# univ_3-7-0-x-rev4.net
KiCad netlist of a schematic drawn in EAGLE
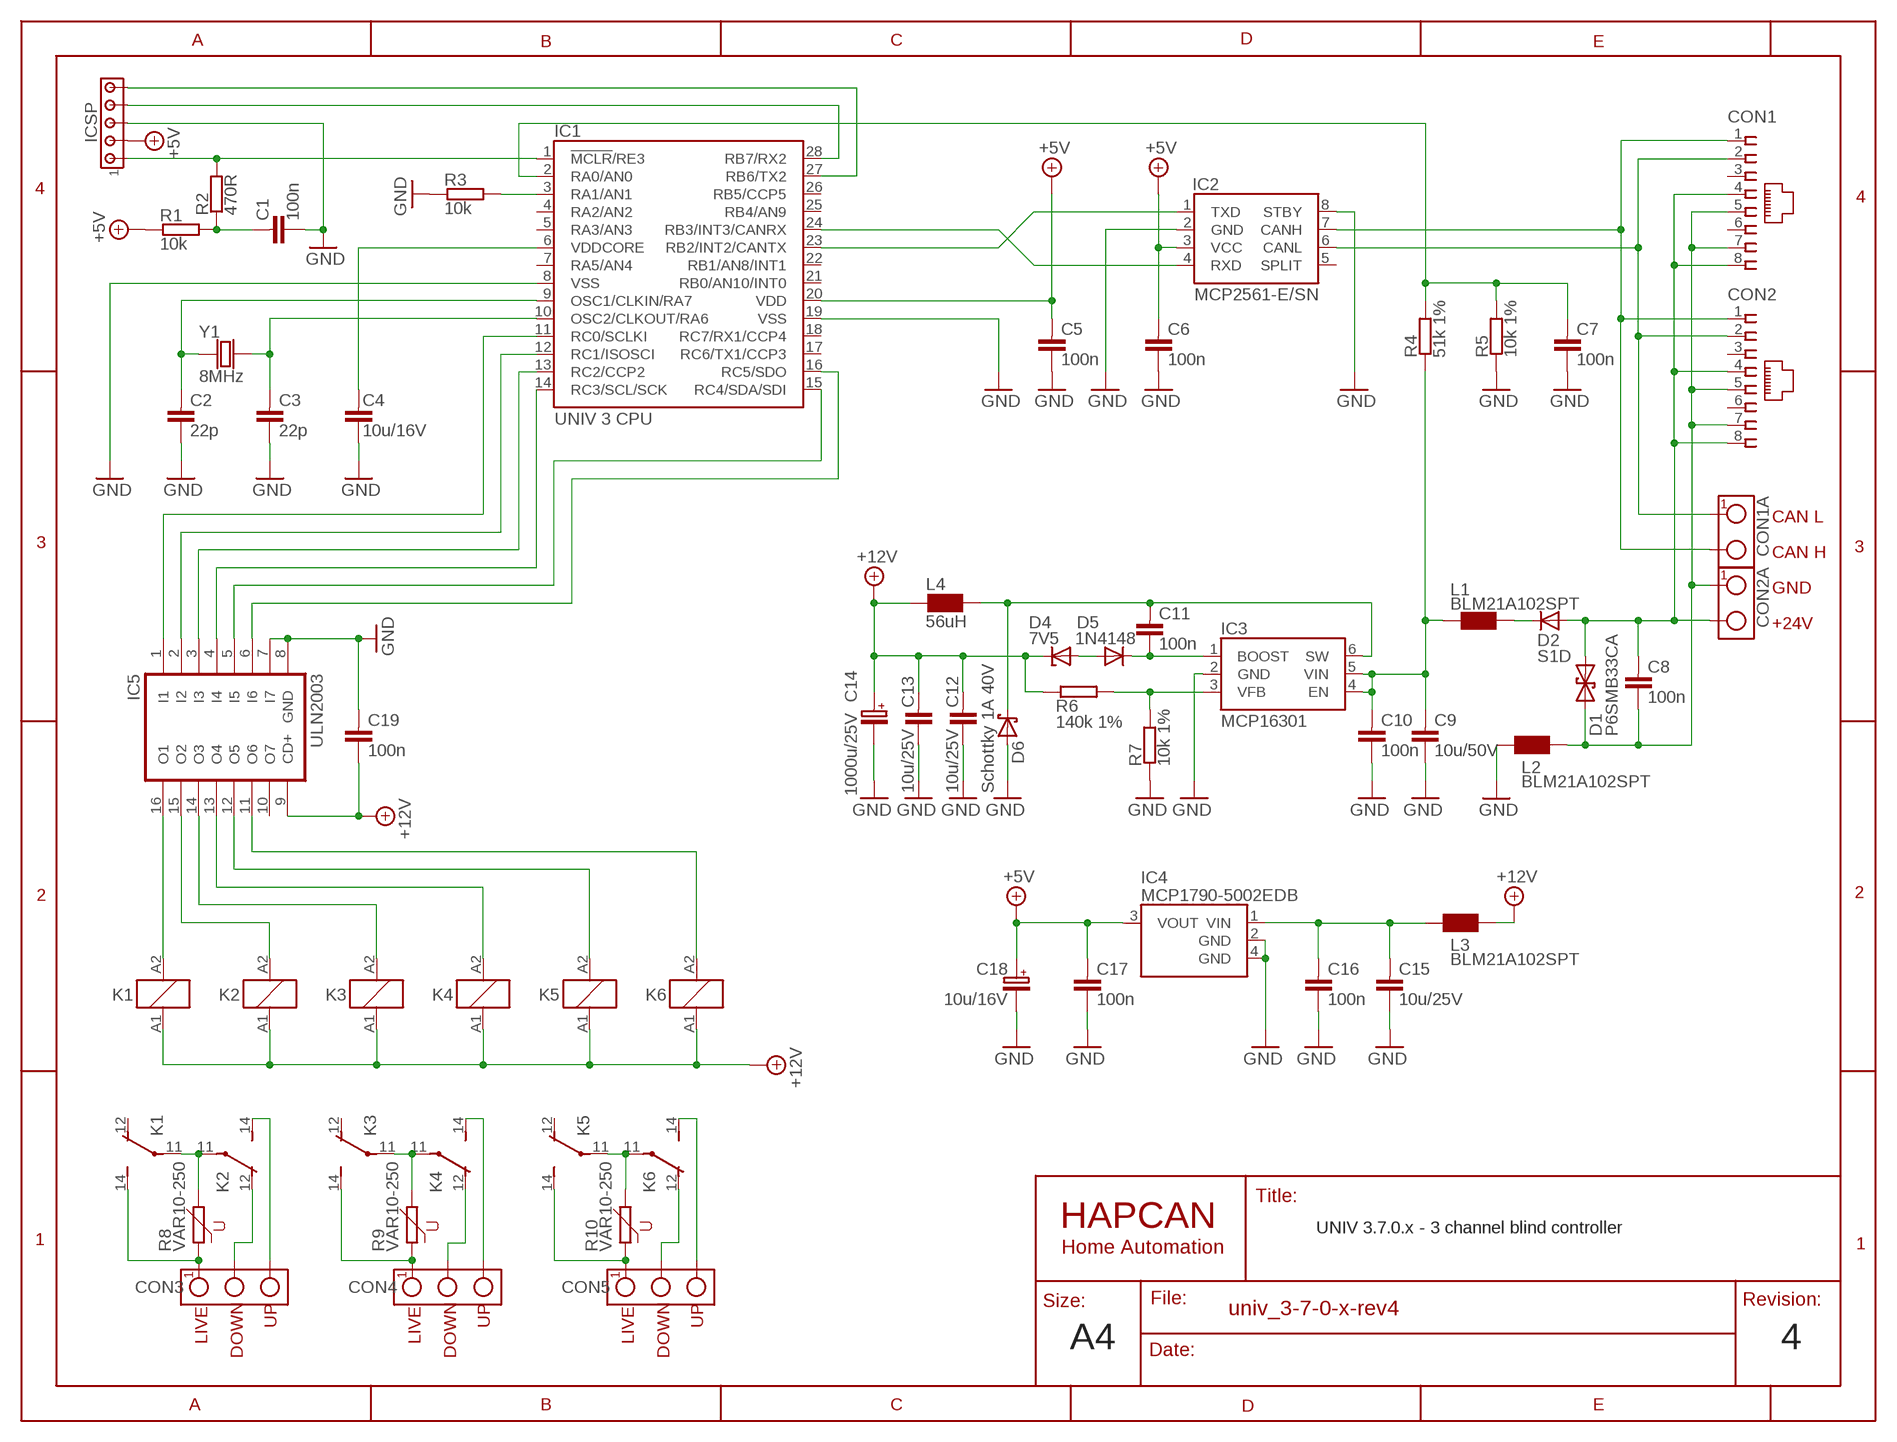
[diagram p0: schematic, sheet 1]

(export (version "E")
  (design (tool "Eeschema 10.0.6"))
  (components
    (comp (ref "C1")
      (value "100n")
      (footprint "eagle-import:0805")
      (libsource (lib "eagle-import") (part "CAPACITOR0805"))
    )
    (comp (ref "C2")
      (value "22p")
      (footprint "eagle-import:0805")
      (libsource (lib "eagle-import") (part "CAPACITOR0805"))
    )
    (comp (ref "C3")
      (value "22p")
      (footprint "eagle-import:0805")
      (libsource (lib "eagle-import") (part "CAPACITOR0805"))
    )
    (comp (ref "C4")
      (value "10u/16V")
      (footprint "eagle-import:0805")
      (libsource (lib "eagle-import") (part "CAPACITOR0805"))
    )
    (comp (ref "C5")
      (value "100n")
      (footprint "eagle-import:0805")
      (libsource (lib "eagle-import") (part "CAPACITOR0805"))
    )
    (comp (ref "C6")
      (value "100n")
      (footprint "eagle-import:0805")
      (libsource (lib "eagle-import") (part "CAPACITOR0805"))
    )
    (comp (ref "C7")
      (value "100n")
      (footprint "eagle-import:0805")
      (libsource (lib "eagle-import") (part "CAPACITOR0805"))
    )
    (comp (ref "C8")
      (value "100n")
      (footprint "eagle-import:0805")
      (libsource (lib "eagle-import") (part "CAPACITOR0805"))
    )
    (comp (ref "C9")
      (value "10u/50V")
      (footprint "eagle-import:1210")
      (libsource (lib "eagle-import") (part "CAPACITOR1210"))
    )
    (comp (ref "C10")
      (value "100n")
      (footprint "eagle-import:0805")
      (libsource (lib "eagle-import") (part "CAPACITOR0805"))
    )
    (comp (ref "C11")
      (value "100n")
      (footprint "eagle-import:0805")
      (libsource (lib "eagle-import") (part "CAPACITOR0805"))
    )
    (comp (ref "C12")
      (value "10u/25V")
      (footprint "eagle-import:1206")
      (libsource (lib "eagle-import") (part "CAPACITOR1206"))
    )
    (comp (ref "C13")
      (value "10u/25V")
      (footprint "eagle-import:1206")
      (libsource (lib "eagle-import") (part "CAPACITOR1206"))
    )
    (comp (ref "C14")
      (value "1000u/25V")
      (footprint "eagle-import:CAP-5X10.5")
      (libsource (lib "eagle-import") (part "CAPACITOR-POLARIZED-5X10.5"))
    )
    (comp (ref "C15")
      (value "10u/25V")
      (footprint "eagle-import:1206")
      (libsource (lib "eagle-import") (part "CAPACITOR1206"))
    )
    (comp (ref "C16")
      (value "100n")
      (footprint "eagle-import:0805")
      (libsource (lib "eagle-import") (part "CAPACITOR0805"))
    )
    (comp (ref "C17")
      (value "100n")
      (footprint "eagle-import:0805")
      (libsource (lib "eagle-import") (part "CAPACITOR0805"))
    )
    (comp (ref "C18")
      (value "10u/16V")
      (footprint "eagle-import:SMC_B")
      (libsource (lib "eagle-import") (part "CAPACITOR-POLARIZED-SMC_B"))
    )
    (comp (ref "C19")
      (value "100n")
      (footprint "eagle-import:0805")
      (libsource (lib "eagle-import") (part "CAPACITOR0805"))
    )
    (comp (ref "CON1")
      (value "RJ45-SOCKET")
      (footprint "eagle-import:RJ45-PCB-SOCKET")
      (libsource (lib "eagle-import") (part "RJ45-SOCKET"))
    )
    (comp (ref "CON1A")
      (value "TERMINAL-2")
      (footprint "eagle-import:ARK2-5X10,5MM")
      (libsource (lib "eagle-import") (part "TERMINAL-2-5X10,5MM"))
    )
    (comp (ref "CON2")
      (value "RJ45-SOCKET")
      (footprint "eagle-import:RJ45-PCB-SOCKET")
      (libsource (lib "eagle-import") (part "RJ45-SOCKET"))
    )
    (comp (ref "CON2A")
      (value "TERMINAL-2")
      (footprint "eagle-import:ARK2-5X10,5MM")
      (libsource (lib "eagle-import") (part "TERMINAL-2-5X10,5MM"))
    )
    (comp (ref "CON3")
      (value "TERMINAL-3-5X10.5MM")
      (footprint "eagle-import:ARK3-5X10.5MM")
      (libsource (lib "eagle-import") (part "TERMINAL-3-5X10.5MM"))
    )
    (comp (ref "CON4")
      (value "TERMINAL-3-5X10.5MM")
      (footprint "eagle-import:ARK3-5X10.5MM")
      (libsource (lib "eagle-import") (part "TERMINAL-3-5X10.5MM"))
    )
    (comp (ref "CON5")
      (value "TERMINAL-3-5X10.5MM")
      (footprint "eagle-import:ARK3-5X10.5MM")
      (libsource (lib "eagle-import") (part "TERMINAL-3-5X10.5MM"))
    )
    (comp (ref "D1")
      (value "P6SMB33CA")
      (footprint "eagle-import:DO-214_TRANSIL2")
      (libsource (lib "eagle-import") (part "DIODE_TRANSIL2"))
    )
    (comp (ref "D2")
      (value "S1D")
      (footprint "eagle-import:DO-214")
      (libsource (lib "eagle-import") (part "DIODE_DO-214"))
    )
    (comp (ref "D4")
      (value "7V5")
      (footprint "eagle-import:SOD-80")
      (libsource (lib "eagle-import") (part "DIODE_ZENER_SOD-80"))
    )
    (comp (ref "D5")
      (value "1N4148")
      (footprint "eagle-import:0805")
      (libsource (lib "eagle-import") (part "DIODE_0805"))
    )
    (comp (ref "D6")
      (value "Schottky 1A 40V")
      (footprint "eagle-import:DO-214")
      (libsource (lib "eagle-import") (part "DIODE_TRANSIL1_DO214"))
    )
    (comp (ref "IC1")
      (value "UNIV 3 CPU")
      (footprint "eagle-import:UNIV3CPU")
      (libsource (lib "eagle-import") (part "UNIV3CPU-I/SO"))
    )
    (comp (ref "IC2")
      (value "MCP2561-E/SN")
      (footprint "eagle-import:SO-08")
      (libsource (lib "eagle-import") (part "MCP2561-E/SN"))
    )
    (comp (ref "IC3")
      (value "MCP16301")
      (footprint "eagle-import:SOT-23-6")
      (libsource (lib "eagle-import") (part "MCP16301SOT23-6"))
    )
    (comp (ref "IC4")
      (value "MCP1790-5002EDB")
      (footprint "eagle-import:SOT-223")
      (libsource (lib "eagle-import") (part "MCP1826SOT223-3"))
    )
    (comp (ref "IC5")
      (value "ULN2003")
      (footprint "eagle-import:SO-16")
      (libsource (lib "eagle-import") (part "ULN2003"))
    )
    (comp (ref "ICSP")
      (value "HEADER5")
      (footprint "eagle-import:SIP-5")
      (libsource (lib "eagle-import") (part "HEADER5"))
    )
    (comp (ref "K1")
      (value "RELAY_SNR_SPDTV")
      (footprint "eagle-import:RELAY_SNR_SPDT_V")
      (libsource (lib "eagle-import") (part "RELAY_SNR_SPDTV"))
    )
    (comp (ref "K2")
      (value "RELAY_SNR_SPDTV")
      (footprint "eagle-import:RELAY_SNR_SPDT_V")
      (libsource (lib "eagle-import") (part "RELAY_SNR_SPDTV"))
    )
    (comp (ref "K3")
      (value "RELAY_SNR_SPDTV")
      (footprint "eagle-import:RELAY_SNR_SPDT_V")
      (libsource (lib "eagle-import") (part "RELAY_SNR_SPDTV"))
    )
    (comp (ref "K4")
      (value "RELAY_SNR_SPDTV")
      (footprint "eagle-import:RELAY_SNR_SPDT_V")
      (libsource (lib "eagle-import") (part "RELAY_SNR_SPDTV"))
    )
    (comp (ref "K5")
      (value "RELAY_SNR_SPDTV")
      (footprint "eagle-import:RELAY_SNR_SPDT_V")
      (libsource (lib "eagle-import") (part "RELAY_SNR_SPDTV"))
    )
    (comp (ref "K6")
      (value "RELAY_SNR_SPDTV")
      (footprint "eagle-import:RELAY_SNR_SPDT_V")
      (libsource (lib "eagle-import") (part "RELAY_SNR_SPDTV"))
    )
    (comp (ref "L1")
      (value "BLM21A102SPT")
      (footprint "eagle-import:0805")
      (libsource (lib "eagle-import") (part "CHOKE0805"))
    )
    (comp (ref "L2")
      (value "BLM21A102SPT")
      (footprint "eagle-import:0805")
      (libsource (lib "eagle-import") (part "CHOKE0805"))
    )
    (comp (ref "L3")
      (value "BLM21A102SPT")
      (footprint "eagle-import:0805")
      (libsource (lib "eagle-import") (part "CHOKE0805"))
    )
    (comp (ref "L4")
      (value "56uH")
      (footprint "eagle-import:CHOKE-DER0705")
      (libsource (lib "eagle-import") (part "CHOKEDER0705"))
    )
    (comp (ref "R1")
      (value "10k")
      (footprint "eagle-import:0805")
      (libsource (lib "eagle-import") (part "RESISTOR0805"))
    )
    (comp (ref "R2")
      (value "470R")
      (footprint "eagle-import:0805")
      (libsource (lib "eagle-import") (part "RESISTOR0805"))
    )
    (comp (ref "R3")
      (value "10k")
      (footprint "eagle-import:0805")
      (libsource (lib "eagle-import") (part "RESISTOR0805"))
    )
    (comp (ref "R4")
      (value "51k 1%")
      (footprint "eagle-import:0805")
      (libsource (lib "eagle-import") (part "RESISTOR0805"))
    )
    (comp (ref "R5")
      (value "10k 1%")
      (footprint "eagle-import:0805")
      (libsource (lib "eagle-import") (part "RESISTOR0805"))
    )
    (comp (ref "R6")
      (value "140k 1%")
      (footprint "eagle-import:0805")
      (libsource (lib "eagle-import") (part "RESISTOR0805"))
    )
    (comp (ref "R7")
      (value "10k 1%")
      (footprint "eagle-import:0805")
      (libsource (lib "eagle-import") (part "RESISTOR0805"))
    )
    (comp (ref "R8")
      (value "VAR10-250")
      (footprint "eagle-import:VARISTOR1")
      (libsource (lib "eagle-import") (part "VARISTOR7.5MM-1"))
    )
    (comp (ref "R9")
      (value "VAR10-250")
      (footprint "eagle-import:VARISTOR1")
      (libsource (lib "eagle-import") (part "VARISTOR7.5MM-1"))
    )
    (comp (ref "R10")
      (value "VAR10-250")
      (footprint "eagle-import:VARISTOR1")
      (libsource (lib "eagle-import") (part "VARISTOR7.5MM-1"))
    )
    (comp (ref "Y1")
      (value "8MHz")
      (footprint "eagle-import:CRYSTAL-HC49V")
      (libsource (lib "eagle-import") (part "CRYSTAL-HC49V"))
    )
  )
  (nets
    (net (code "1") (name "+5V") (class "Default")
      (node (ref "C17") (pin "1") (pinfunction "1_1") (pintype "passive"))
      (node (ref "C18") (pin "+") (pinfunction "1_+") (pintype "passive"))
      (node (ref "C5") (pin "1") (pinfunction "1_1") (pintype "passive"))
      (node (ref "C6") (pin "1") (pinfunction "1_1") (pintype "passive"))
      (node (ref "IC1") (pin "20") (pinfunction "VDD_20") (pintype "bidirectional"))
      (node (ref "IC2") (pin "3") (pinfunction "VCC_3") (pintype "bidirectional"))
      (node (ref "IC4") (pin "3") (pinfunction "VOUT_3") (pintype "bidirectional"))
      (node (ref "ICSP") (pin "2") (pinfunction "2_2") (pintype "passive"))
      (node (ref "R1") (pin "1") (pinfunction "1_1") (pintype "passive"))
    )
    (net (code "2") (name "+12V") (class "Default")
      (node (ref "C12") (pin "1") (pinfunction "1_1") (pintype "passive"))
      (node (ref "C13") (pin "1") (pinfunction "1_1") (pintype "passive"))
      (node (ref "C14") (pin "+") (pinfunction "1_+") (pintype "passive"))
      (node (ref "C19") (pin "2") (pinfunction "2_2") (pintype "passive"))
      (node (ref "D4") (pin "C") (pinfunction "C_C") (pintype "passive"))
      (node (ref "IC5") (pin "9") (pinfunction "CD+_9") (pintype "passive"))
      (node (ref "K1") (pin "A1") (pinfunction "1_A1") (pintype "passive"))
      (node (ref "K2") (pin "A1") (pinfunction "1_A1") (pintype "passive"))
      (node (ref "K3") (pin "A1") (pinfunction "1_A1") (pintype "passive"))
      (node (ref "K4") (pin "A1") (pinfunction "1_A1") (pintype "passive"))
      (node (ref "K5") (pin "A1") (pinfunction "1_A1") (pintype "passive"))
      (node (ref "K6") (pin "A1") (pinfunction "1_A1") (pintype "passive"))
      (node (ref "L3") (pin "2") (pinfunction "2_2") (pintype "passive"))
      (node (ref "L4") (pin "1") (pinfunction "1_1") (pintype "passive"))
      (node (ref "R6") (pin "1") (pinfunction "1_1") (pintype "passive"))
    )
    (net (code "3") (name "GND") (class "Default")
      (node (ref "C1") (pin "2") (pinfunction "2_2") (pintype "passive"))
      (node (ref "C10") (pin "2") (pinfunction "2_2") (pintype "passive"))
      (node (ref "C12") (pin "2") (pinfunction "2_2") (pintype "passive"))
      (node (ref "C13") (pin "2") (pinfunction "2_2") (pintype "passive"))
      (node (ref "C14") (pin "-") (pinfunction "2_-") (pintype "passive"))
      (node (ref "C15") (pin "2") (pinfunction "2_2") (pintype "passive"))
      (node (ref "C16") (pin "2") (pinfunction "2_2") (pintype "passive"))
      (node (ref "C17") (pin "2") (pinfunction "2_2") (pintype "passive"))
      (node (ref "C18") (pin "-") (pinfunction "2_-") (pintype "passive"))
      (node (ref "C19") (pin "1") (pinfunction "1_1") (pintype "passive"))
      (node (ref "C2") (pin "2") (pinfunction "2_2") (pintype "passive"))
      (node (ref "C3") (pin "2") (pinfunction "2_2") (pintype "passive"))
      (node (ref "C4") (pin "2") (pinfunction "2_2") (pintype "passive"))
      (node (ref "C5") (pin "2") (pinfunction "2_2") (pintype "passive"))
      (node (ref "C6") (pin "2") (pinfunction "2_2") (pintype "passive"))
      (node (ref "C7") (pin "2") (pinfunction "2_2") (pintype "passive"))
      (node (ref "C9") (pin "2") (pinfunction "2_2") (pintype "passive"))
      (node (ref "D6") (pin "A") (pinfunction "A_A") (pintype "passive"))
      (node (ref "IC1") (pin "19") (pinfunction "VSS_19") (pintype "bidirectional"))
      (node (ref "IC1") (pin "8") (pinfunction "VSS_8") (pintype "bidirectional"))
      (node (ref "IC2") (pin "2") (pinfunction "GND_2") (pintype "bidirectional"))
      (node (ref "IC2") (pin "8") (pinfunction "STBY_8") (pintype "bidirectional"))
      (node (ref "IC3") (pin "2") (pinfunction "GND_2") (pintype "bidirectional"))
      (node (ref "IC4") (pin "2") (pinfunction "GND_2") (pintype "bidirectional"))
      (node (ref "IC4") (pin "4") (pinfunction "GND_4") (pintype "bidirectional"))
      (node (ref "IC5") (pin "7") (pinfunction "I7_7") (pintype "input"))
      (node (ref "IC5") (pin "8") (pinfunction "GND_8") (pintype "power_in"))
      (node (ref "ICSP") (pin "3") (pinfunction "3_3") (pintype "passive"))
      (node (ref "L2") (pin "1") (pinfunction "1_1") (pintype "passive"))
      (node (ref "R3") (pin "1") (pinfunction "1_1") (pintype "passive"))
      (node (ref "R5") (pin "1") (pinfunction "1_1") (pintype "passive"))
      (node (ref "R7") (pin "1") (pinfunction "1_1") (pintype "passive"))
    )
    (net (code "4") (name "Net-(C1-Pad1)") (class "Default")
      (node (ref "C1") (pin "1") (pinfunction "1_1") (pintype "passive"))
      (node (ref "R1") (pin "2") (pinfunction "2_2") (pintype "passive"))
      (node (ref "R2") (pin "1") (pinfunction "1_1") (pintype "passive"))
    )
    (net (code "5") (name "Net-(D1-1)") (class "Default")
      (node (ref "C8") (pin "2") (pinfunction "2_2") (pintype "passive"))
      (node (ref "CON1") (pin "5") (pinfunction "5_5") (pintype "passive"))
      (node (ref "CON1") (pin "7") (pinfunction "7_7") (pintype "passive"))
      (node (ref "CON2") (pin "5") (pinfunction "5_5") (pintype "passive"))
      (node (ref "CON2") (pin "7") (pinfunction "7_7") (pintype "passive"))
      (node (ref "CON2A") (pin "1") (pinfunction "1_1") (pintype "passive"))
      (node (ref "D1") (pin "A") (pinfunction "1_A") (pintype "passive"))
      (node (ref "L2") (pin "2") (pinfunction "2_2") (pintype "passive"))
    )
    (net (code "6") (name "Net-(D1-2)") (class "Default")
      (node (ref "C8") (pin "1") (pinfunction "1_1") (pintype "passive"))
      (node (ref "CON1") (pin "4") (pinfunction "4_4") (pintype "passive"))
      (node (ref "CON1") (pin "8") (pinfunction "8_8") (pintype "passive"))
      (node (ref "CON2") (pin "4") (pinfunction "4_4") (pintype "passive"))
      (node (ref "CON2") (pin "8") (pinfunction "8_8") (pintype "passive"))
      (node (ref "CON2A") (pin "2") (pinfunction "2_2") (pintype "passive"))
      (node (ref "D1") (pin "C") (pinfunction "2_C") (pintype "passive"))
      (node (ref "D2") (pin "A") (pinfunction "A_A") (pintype "passive"))
    )
    (net (code "7") (name "Net-(D2-PadC)") (class "Default")
      (node (ref "D2") (pin "C") (pinfunction "C_C") (pintype "passive"))
      (node (ref "L1") (pin "2") (pinfunction "2_2") (pintype "passive"))
    )
    (net (code "8") (name "Net-(D5-A)") (class "Default")
      (node (ref "D4") (pin "A") (pinfunction "A_A") (pintype "passive"))
      (node (ref "D5") (pin "2") (pinfunction "A_2") (pintype "passive"))
    )
    (net (code "9") (name "Net-(D5-C)") (class "Default")
      (node (ref "C11") (pin "2") (pinfunction "2_2") (pintype "passive"))
      (node (ref "D5") (pin "1") (pinfunction "C_1") (pintype "passive"))
      (node (ref "IC3") (pin "1") (pinfunction "BOOST_1") (pintype "bidirectional"))
    )
    (net (code "10") (name "Net-(IC1-OSC1{slash}CLKIN{slash}RA7)") (class "Default")
      (node (ref "C2") (pin "1") (pinfunction "1_1") (pintype "passive"))
      (node (ref "IC1") (pin "9") (pinfunction "OSC1/CLKIN/RA7_9") (pintype "bidirectional"))
      (node (ref "Y1") (pin "1") (pinfunction "1_1") (pintype "passive"))
    )
    (net (code "11") (name "Net-(IC1-OSC2{slash}CLKOUT{slash}RA6)") (class "Default")
      (node (ref "C3") (pin "1") (pinfunction "1_1") (pintype "passive"))
      (node (ref "IC1") (pin "10") (pinfunction "OSC2/CLKOUT/RA6_10") (pintype "bidirectional"))
      (node (ref "Y1") (pin "2") (pinfunction "2_2") (pintype "passive"))
    )
    (net (code "12") (name "Net-(IC1-RA0{slash}AN0)") (class "Default")
      (node (ref "C7") (pin "1") (pinfunction "1_1") (pintype "passive"))
      (node (ref "IC1") (pin "2") (pinfunction "RA0/AN0_2") (pintype "bidirectional"))
      (node (ref "R4") (pin "2") (pinfunction "2_2") (pintype "passive"))
      (node (ref "R5") (pin "2") (pinfunction "2_2") (pintype "passive"))
    )
    (net (code "13") (name "Net-(IC1-RA1{slash}AN1)") (class "Default")
      (node (ref "IC1") (pin "3") (pinfunction "RA1/AN1_3") (pintype "bidirectional"))
      (node (ref "R3") (pin "2") (pinfunction "2_2") (pintype "passive"))
    )
    (net (code "14") (name "Net-(IC1-RB2{slash}INT2{slash}CANTX)") (class "Default")
      (node (ref "IC1") (pin "23") (pinfunction "RB2/INT2/CANTX_23") (pintype "bidirectional"))
      (node (ref "IC2") (pin "1") (pinfunction "TXD_1") (pintype "bidirectional"))
    )
    (net (code "15") (name "Net-(IC1-RB3{slash}INT3{slash}CANRX)") (class "Default")
      (node (ref "IC1") (pin "24") (pinfunction "RB3/INT3/CANRX_24") (pintype "bidirectional"))
      (node (ref "IC2") (pin "4") (pinfunction "RXD_4") (pintype "bidirectional"))
    )
    (net (code "16") (name "Net-(IC1-RB6{slash}TX2)") (class "Default")
      (node (ref "IC1") (pin "27") (pinfunction "RB6/TX2_27") (pintype "bidirectional"))
      (node (ref "ICSP") (pin "5") (pinfunction "5_5") (pintype "passive"))
    )
    (net (code "17") (name "Net-(IC1-RB7{slash}RX2)") (class "Default")
      (node (ref "IC1") (pin "28") (pinfunction "RB7/RX2_28") (pintype "bidirectional"))
      (node (ref "ICSP") (pin "4") (pinfunction "4_4") (pintype "passive"))
    )
    (net (code "18") (name "Net-(IC1-RC0{slash}SCLKI)") (class "Default")
      (node (ref "IC1") (pin "11") (pinfunction "RC0/SCLKI_11") (pintype "bidirectional"))
      (node (ref "IC5") (pin "1") (pinfunction "I1_1") (pintype "input"))
    )
    (net (code "19") (name "Net-(IC1-RC1{slash}ISOSCI)") (class "Default")
      (node (ref "IC1") (pin "12") (pinfunction "RC1/ISOSCI_12") (pintype "bidirectional"))
      (node (ref "IC5") (pin "2") (pinfunction "I2_2") (pintype "input"))
    )
    (net (code "20") (name "Net-(IC1-RC2{slash}CCP2)") (class "Default")
      (node (ref "IC1") (pin "13") (pinfunction "RC2/CCP2_13") (pintype "bidirectional"))
      (node (ref "IC5") (pin "3") (pinfunction "I3_3") (pintype "input"))
    )
    (net (code "21") (name "Net-(IC1-RC3{slash}SCL{slash}SCK)") (class "Default")
      (node (ref "IC1") (pin "14") (pinfunction "RC3/SCL/SCK_14") (pintype "bidirectional"))
      (node (ref "IC5") (pin "4") (pinfunction "I4_4") (pintype "input"))
    )
    (net (code "22") (name "Net-(IC1-RC4{slash}SDA{slash}SDI)") (class "Default")
      (node (ref "IC1") (pin "15") (pinfunction "RC4/SDA/SDI_15") (pintype "bidirectional"))
      (node (ref "IC5") (pin "5") (pinfunction "I5_5") (pintype "input"))
    )
    (net (code "23") (name "Net-(IC1-RC5{slash}SDO)") (class "Default")
      (node (ref "IC1") (pin "16") (pinfunction "RC5/SDO_16") (pintype "bidirectional"))
      (node (ref "IC5") (pin "6") (pinfunction "I6_6") (pintype "input"))
    )
    (net (code "24") (name "Net-(IC1-VDDCORE)") (class "Default")
      (node (ref "C4") (pin "1") (pinfunction "1_1") (pintype "passive"))
      (node (ref "IC1") (pin "6") (pinfunction "VDDCORE_6") (pintype "bidirectional"))
    )
    (net (code "25") (name "Net-(IC1-~{MCLR}{slash}RE3)") (class "Default")
      (node (ref "IC1") (pin "1") (pinfunction "~{MCLR}/RE3_1") (pintype "bidirectional"))
      (node (ref "ICSP") (pin "1") (pinfunction "1_1") (pintype "passive"))
      (node (ref "R2") (pin "2") (pinfunction "2_2") (pintype "passive"))
    )
    (net (code "26") (name "Net-(IC2-CANH)") (class "Default")
      (node (ref "CON1") (pin "1") (pinfunction "1_1") (pintype "passive"))
      (node (ref "CON1A") (pin "2") (pinfunction "2_2") (pintype "passive"))
      (node (ref "CON2") (pin "1") (pinfunction "1_1") (pintype "passive"))
      (node (ref "IC2") (pin "7") (pinfunction "CANH_7") (pintype "bidirectional"))
    )
    (net (code "27") (name "Net-(IC2-CANL)") (class "Default")
      (node (ref "CON1") (pin "2") (pinfunction "2_2") (pintype "passive"))
      (node (ref "CON1A") (pin "1") (pinfunction "1_1") (pintype "passive"))
      (node (ref "CON2") (pin "2") (pinfunction "2_2") (pintype "passive"))
      (node (ref "IC2") (pin "6") (pinfunction "CANL_6") (pintype "bidirectional"))
    )
    (net (code "28") (name "Net-(IC3-EN)") (class "Default")
      (node (ref "C10") (pin "1") (pinfunction "1_1") (pintype "passive"))
      (node (ref "C9") (pin "1") (pinfunction "1_1") (pintype "passive"))
      (node (ref "IC3") (pin "4") (pinfunction "EN_4") (pintype "bidirectional"))
      (node (ref "IC3") (pin "5") (pinfunction "VIN_5") (pintype "bidirectional"))
      (node (ref "L1") (pin "1") (pinfunction "1_1") (pintype "passive"))
      (node (ref "R4") (pin "1") (pinfunction "1_1") (pintype "passive"))
    )
    (net (code "29") (name "Net-(IC3-SW)") (class "Default")
      (node (ref "C11") (pin "1") (pinfunction "1_1") (pintype "passive"))
      (node (ref "D6") (pin "C") (pinfunction "C_C") (pintype "passive"))
      (node (ref "IC3") (pin "6") (pinfunction "SW_6") (pintype "bidirectional"))
      (node (ref "L4") (pin "2") (pinfunction "2_2") (pintype "passive"))
    )
    (net (code "30") (name "Net-(IC3-VFB)") (class "Default")
      (node (ref "IC3") (pin "3") (pinfunction "VFB_3") (pintype "bidirectional"))
      (node (ref "R6") (pin "2") (pinfunction "2_2") (pintype "passive"))
      (node (ref "R7") (pin "2") (pinfunction "2_2") (pintype "passive"))
    )
    (net (code "31") (name "Net-(IC4-VIN)") (class "Default")
      (node (ref "C15") (pin "1") (pinfunction "1_1") (pintype "passive"))
      (node (ref "C16") (pin "1") (pinfunction "1_1") (pintype "passive"))
      (node (ref "IC4") (pin "1") (pinfunction "VIN_1") (pintype "bidirectional"))
      (node (ref "L3") (pin "1") (pinfunction "1_1") (pintype "passive"))
    )
    (net (code "32") (name "Net-(IC5-O1)") (class "Default")
      (node (ref "IC5") (pin "16") (pinfunction "O1_16") (pintype "open_collector"))
      (node (ref "K1") (pin "A2") (pinfunction "2_A2") (pintype "passive"))
    )
    (net (code "33") (name "Net-(IC5-O2)") (class "Default")
      (node (ref "IC5") (pin "15") (pinfunction "O2_15") (pintype "open_collector"))
      (node (ref "K2") (pin "A2") (pinfunction "2_A2") (pintype "passive"))
    )
    (net (code "34") (name "Net-(IC5-O3)") (class "Default")
      (node (ref "IC5") (pin "14") (pinfunction "O3_14") (pintype "open_collector"))
      (node (ref "K3") (pin "A2") (pinfunction "2_A2") (pintype "passive"))
    )
    (net (code "35") (name "Net-(IC5-O4)") (class "Default")
      (node (ref "IC5") (pin "13") (pinfunction "O4_13") (pintype "open_collector"))
      (node (ref "K4") (pin "A2") (pinfunction "2_A2") (pintype "passive"))
    )
    (net (code "36") (name "Net-(IC5-O5)") (class "Default")
      (node (ref "IC5") (pin "12") (pinfunction "O5_12") (pintype "open_collector"))
      (node (ref "K5") (pin "A2") (pinfunction "2_A2") (pintype "passive"))
    )
    (net (code "37") (name "Net-(IC5-O6)") (class "Default")
      (node (ref "IC5") (pin "11") (pinfunction "O6_11") (pintype "open_collector"))
      (node (ref "K6") (pin "A2") (pinfunction "2_A2") (pintype "passive"))
    )
    (net (code "38") (name "Net-(K1B-COM)") (class "Default")
      (node (ref "K1") (pin "11") (pinfunction "COM_11") (pintype "passive"))
      (node (ref "K2") (pin "11") (pinfunction "COM_11") (pintype "passive"))
      (node (ref "R8") (pin "2") (pinfunction "2_2") (pintype "passive"))
    )
    (net (code "39") (name "Net-(K1B-NO)") (class "Default")
      (node (ref "CON3") (pin "1") (pinfunction "1_1") (pintype "passive"))
      (node (ref "K1") (pin "14") (pinfunction "NO_14") (pintype "passive"))
      (node (ref "R8") (pin "1") (pinfunction "1_1") (pintype "passive"))
    )
    (net (code "40") (name "Net-(K2B-NC)") (class "Default")
      (node (ref "CON3") (pin "2") (pinfunction "2_2") (pintype "passive"))
      (node (ref "K2") (pin "12") (pinfunction "NC_12") (pintype "passive"))
    )
    (net (code "41") (name "Net-(K2B-NO)") (class "Default")
      (node (ref "CON3") (pin "3") (pinfunction "3_3") (pintype "passive"))
      (node (ref "K2") (pin "14") (pinfunction "NO_14") (pintype "passive"))
    )
    (net (code "42") (name "Net-(K3B-COM)") (class "Default")
      (node (ref "K3") (pin "11") (pinfunction "COM_11") (pintype "passive"))
      (node (ref "K4") (pin "11") (pinfunction "COM_11") (pintype "passive"))
      (node (ref "R9") (pin "2") (pinfunction "2_2") (pintype "passive"))
    )
    (net (code "43") (name "Net-(K3B-NO)") (class "Default")
      (node (ref "CON4") (pin "1") (pinfunction "1_1") (pintype "passive"))
      (node (ref "K3") (pin "14") (pinfunction "NO_14") (pintype "passive"))
      (node (ref "R9") (pin "1") (pinfunction "1_1") (pintype "passive"))
    )
    (net (code "44") (name "Net-(K4B-NC)") (class "Default")
      (node (ref "CON4") (pin "2") (pinfunction "2_2") (pintype "passive"))
      (node (ref "K4") (pin "12") (pinfunction "NC_12") (pintype "passive"))
    )
    (net (code "45") (name "Net-(K4B-NO)") (class "Default")
      (node (ref "CON4") (pin "3") (pinfunction "3_3") (pintype "passive"))
      (node (ref "K4") (pin "14") (pinfunction "NO_14") (pintype "passive"))
    )
    (net (code "46") (name "Net-(K5B-COM)") (class "Default")
      (node (ref "K5") (pin "11") (pinfunction "COM_11") (pintype "passive"))
      (node (ref "K6") (pin "11") (pinfunction "COM_11") (pintype "passive"))
      (node (ref "R10") (pin "2") (pinfunction "2_2") (pintype "passive"))
    )
    (net (code "47") (name "Net-(K5B-NO)") (class "Default")
      (node (ref "CON5") (pin "1") (pinfunction "1_1") (pintype "passive"))
      (node (ref "K5") (pin "14") (pinfunction "NO_14") (pintype "passive"))
      (node (ref "R10") (pin "1") (pinfunction "1_1") (pintype "passive"))
    )
    (net (code "48") (name "Net-(K6B-NC)") (class "Default")
      (node (ref "CON5") (pin "2") (pinfunction "2_2") (pintype "passive"))
      (node (ref "K6") (pin "12") (pinfunction "NC_12") (pintype "passive"))
    )
    (net (code "49") (name "Net-(K6B-NO)") (class "Default")
      (node (ref "CON5") (pin "3") (pinfunction "3_3") (pintype "passive"))
      (node (ref "K6") (pin "14") (pinfunction "NO_14") (pintype "passive"))
    )
    (net (code "50") (name "unconnected-(CON1-Pad3)") (class "Default")
      (node (ref "CON1") (pin "3") (pinfunction "3_3") (pintype "passive"))
    )
    (net (code "51") (name "unconnected-(CON1-Pad6)") (class "Default")
      (node (ref "CON1") (pin "6") (pinfunction "6_6") (pintype "passive"))
    )
    (net (code "52") (name "unconnected-(CON2-Pad3)") (class "Default")
      (node (ref "CON2") (pin "3") (pinfunction "3_3") (pintype "passive"))
    )
    (net (code "53") (name "unconnected-(CON2-Pad6)") (class "Default")
      (node (ref "CON2") (pin "6") (pinfunction "6_6") (pintype "passive"))
    )
    (net (code "54") (name "unconnected-(IC1-RA2{slash}AN2-Pad4)") (class "Default")
      (node (ref "IC1") (pin "4") (pinfunction "RA2/AN2_4") (pintype "bidirectional"))
    )
    (net (code "55") (name "unconnected-(IC1-RA3{slash}AN3-Pad5)") (class "Default")
      (node (ref "IC1") (pin "5") (pinfunction "RA3/AN3_5") (pintype "bidirectional"))
    )
    (net (code "56") (name "unconnected-(IC1-RA5{slash}AN4-Pad7)") (class "Default")
      (node (ref "IC1") (pin "7") (pinfunction "RA5/AN4_7") (pintype "bidirectional"))
    )
    (net (code "57") (name "unconnected-(IC1-RB0{slash}AN10{slash}INT0-Pad21)") (class "Default")
      (node (ref "IC1") (pin "21") (pinfunction "RB0/AN10/INT0_21") (pintype "bidirectional"))
    )
    (net (code "58") (name "unconnected-(IC1-RB1{slash}AN8{slash}INT1-Pad22)") (class "Default")
      (node (ref "IC1") (pin "22") (pinfunction "RB1/AN8/INT1_22") (pintype "bidirectional"))
    )
    (net (code "59") (name "unconnected-(IC1-RB4{slash}AN9-Pad25)") (class "Default")
      (node (ref "IC1") (pin "25") (pinfunction "RB4/AN9_25") (pintype "bidirectional"))
    )
    (net (code "60") (name "unconnected-(IC1-RB5{slash}CCP5-Pad26)") (class "Default")
      (node (ref "IC1") (pin "26") (pinfunction "RB5/CCP5_26") (pintype "bidirectional"))
    )
    (net (code "61") (name "unconnected-(IC1-RC6{slash}TX1{slash}CCP3-Pad17)") (class "Default")
      (node (ref "IC1") (pin "17") (pinfunction "RC6/TX1/CCP3_17") (pintype "bidirectional"))
    )
    (net (code "62") (name "unconnected-(IC1-RC7{slash}RX1{slash}CCP4-Pad18)") (class "Default")
      (node (ref "IC1") (pin "18") (pinfunction "RC7/RX1/CCP4_18") (pintype "bidirectional"))
    )
    (net (code "63") (name "unconnected-(IC2-SPLIT-Pad5)") (class "Default")
      (node (ref "IC2") (pin "5") (pinfunction "SPLIT_5") (pintype "bidirectional"))
    )
    (net (code "64") (name "unconnected-(IC5-O7-Pad10)") (class "Default")
      (node (ref "IC5") (pin "10") (pinfunction "O7_10") (pintype "open_collector"))
    )
    (net (code "65") (name "unconnected-(K1B-NC-Pad12)") (class "Default")
      (node (ref "K1") (pin "12") (pinfunction "NC_12") (pintype "passive"))
    )
    (net (code "66") (name "unconnected-(K3B-NC-Pad12)") (class "Default")
      (node (ref "K3") (pin "12") (pinfunction "NC_12") (pintype "passive"))
    )
    (net (code "67") (name "unconnected-(K5B-NC-Pad12)") (class "Default")
      (node (ref "K5") (pin "12") (pinfunction "NC_12") (pintype "passive"))
    )
  )
)
